# schematic.net
KiCad netlist of a schematic drawn in Altium Designer
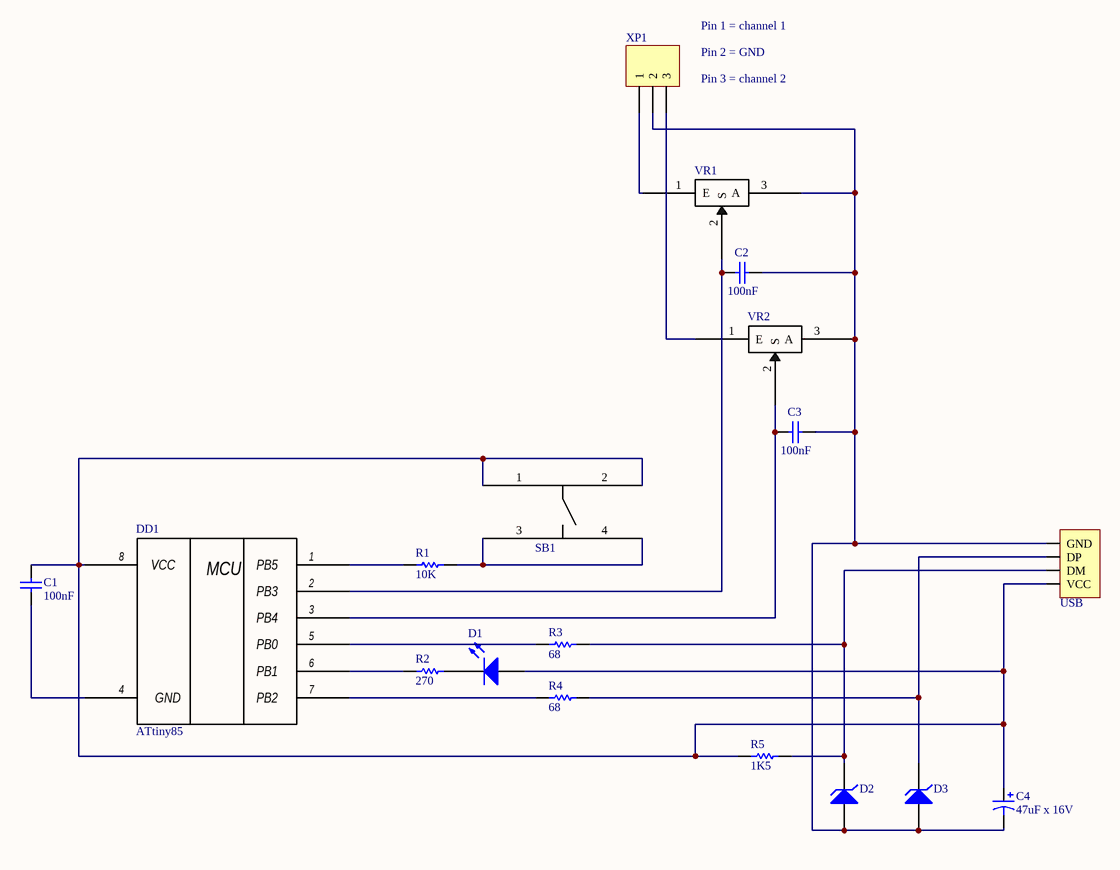
[diagram p0: schematic.SchDoc]

(export (version "E")
  (design (tool "Eeschema 10.0.6"))
  (components
    (comp (ref "C1")
      (value "100nF")
      (footprint "RAD-0.1")
      (description "Capacitor")
      (fields (field (name "PUBLISHER") "Altium Limited"))
      (libsource (lib "Miscellaneous Devices") (part "Cap"))
    )
    (comp (ref "C2")
      (value "100nF")
      (footprint "RAD-0.1")
      (description "Capacitor")
      (fields (field (name "PUBLISHER") "Altium Limited"))
      (libsource (lib "Miscellaneous Devices") (part "Cap"))
    )
    (comp (ref "C3")
      (value "100nF")
      (footprint "RAD-0.1")
      (description "Capacitor")
      (fields (field (name "PUBLISHER") "Altium Limited"))
      (libsource (lib "Miscellaneous Devices") (part "Cap"))
    )
    (comp (ref "C4")
      (value "47uF x 16V")
      (footprint "HDR1X2")
      (description "Polarized Capacitor (Radial)")
      (fields (field (name "PUBLISHER") "Altium Limited"))
      (libsource (lib "Miscellaneous Devices") (part "Cap Pol1"))
    )
    (comp (ref "D1")
      (value "~")
      (footprint "HDR1X2")
      (description "Typical RED GaAs LED")
      (fields (field (name "PUBLISHER") "Altium Limited"))
      (libsource (lib "Miscellaneous Devices") (part "LED1"))
    )
    (comp (ref "D2")
      (value "Zener")
      (footprint "DO-35")
      (description "Zener Diode")
      (fields (field (name "PUBLISHER") "Altium Limited"))
      (libsource (lib "Miscellaneous Devices") (part "D Zener"))
    )
    (comp (ref "D3")
      (value "Zener")
      (footprint "DO-35")
      (description "Zener Diode")
      (fields (field (name "PUBLISHER") "Altium Limited"))
      (libsource (lib "Miscellaneous Devices") (part "D Zener"))
    )
    (comp (ref "DD1")
      (value "ATtiny85")
      (footprint "DIP-8-300")
      (description "8-bit AVR MCU")
      (fields (field (name "PUBLISHER") "Victor Grigoryev"))
      (libsource (lib "Schlib1") (part "ATtiny85"))
    )
    (comp (ref "R1")
      (value "10K")
      (footprint "AXIAL-0.3")
      (description "Resistor")
      (fields (field (name "PUBLISHER") "Altium Limited"))
      (libsource (lib "Miscellaneous Devices") (part "Res1"))
    )
    (comp (ref "R2")
      (value "270")
      (footprint "AXIAL-0.3")
      (description "Resistor")
      (fields (field (name "PUBLISHER") "Altium Limited"))
      (libsource (lib "Miscellaneous Devices") (part "Res1"))
    )
    (comp (ref "R3")
      (value "68")
      (footprint "AXIAL-0.3")
      (description "Resistor")
      (fields (field (name "PUBLISHER") "Altium Limited"))
      (libsource (lib "Miscellaneous Devices") (part "Res1"))
    )
    (comp (ref "R4")
      (value "68")
      (footprint "AXIAL-0.3")
      (description "Resistor")
      (fields (field (name "PUBLISHER") "Altium Limited"))
      (libsource (lib "Miscellaneous Devices") (part "Res1"))
    )
    (comp (ref "R5")
      (value "1K5")
      (footprint "AXIAL-0.3")
      (description "Resistor")
      (fields (field (name "PUBLISHER") "Altium Limited"))
      (libsource (lib "Miscellaneous Devices") (part "Res1"))
    )
    (comp (ref "SB1")
      (value "Button TACT-64K")
      (footprint "Button TACT-64K")
      (description "My standart switch button")
      (fields (field (name "PUBLISHER") "Victor Grigoryev"))
      (libsource (lib "Schlib1") (part "Button TACT-64K"))
    )
    (comp (ref "USB")
      (value "USB_TypeB")
      (footprint "PCB_USB:USB_TypeB")
      (description "USB")
      (libsource (lib "SCH_USB") (part "USB_TypeB"))
    )
    (comp (ref "VR1")
      (value "Potentiometer")
      (footprint "Potentiometer")
      (fields (field (name "PUBLISHER") "Victor Grigoryev"))
      (libsource (lib "Schlib1") (part "Potentiometer"))
    )
    (comp (ref "VR2")
      (value "Potentiometer")
      (footprint "Potentiometer")
      (fields (field (name "PUBLISHER") "Victor Grigoryev"))
      (libsource (lib "Schlib1") (part "Potentiometer"))
    )
    (comp (ref "XP1")
      (value "WF-03R")
      (footprint "HDR1X3")
      (description "Header, 3-Pin")
      (fields (field (name "PUBLISHER") "Altium Limited"))
      (libsource (lib "Miscellaneous Connectors") (part "Header 3"))
    )
  )
  (nets
    (net (code "1") (name "Net-(D1-A)") (class "Default")
      (node (ref "C1") (pin "2") (pinfunction "2_2") (pintype "passive"))
      (node (ref "C4") (pin "1") (pinfunction "1_1") (pintype "passive"))
      (node (ref "D1") (pin "1") (pinfunction "A_1") (pintype "passive"))
      (node (ref "DD1") (pin "8") (pinfunction "VCC_8") (pintype "passive"))
      (node (ref "R5") (pin "2") (pinfunction "2_2") (pintype "passive"))
      (node (ref "SB1") (pin "1") (pinfunction "1_1") (pintype "passive"))
      (node (ref "SB1") (pin "2") (pinfunction "2_2") (pintype "passive"))
      (node (ref "USB") (pin "1") (pinfunction "VCC_1") (pintype "passive"))
    )
    (net (code "2") (name "Net-(D1-K)") (class "Default")
      (node (ref "D1") (pin "2") (pinfunction "K_2") (pintype "passive"))
      (node (ref "R2") (pin "2") (pinfunction "2_2") (pintype "passive"))
    )
    (net (code "3") (name "Net-(D2-A)") (class "Default")
      (node (ref "C2") (pin "1") (pinfunction "1_1") (pintype "passive"))
      (node (ref "C3") (pin "1") (pinfunction "1_1") (pintype "passive"))
      (node (ref "C4") (pin "2") (pinfunction "2_2") (pintype "passive"))
      (node (ref "D2") (pin "1") (pinfunction "A_1") (pintype "passive"))
      (node (ref "D3") (pin "1") (pinfunction "A_1") (pintype "passive"))
      (node (ref "USB") (pin "4") (pinfunction "GND_4") (pintype "passive"))
      (node (ref "VR1") (pin "3") (pinfunction "A_3") (pintype "passive"))
      (node (ref "VR2") (pin "3") (pinfunction "A_3") (pintype "passive"))
      (node (ref "XP1") (pin "2") (pinfunction "2_2") (pintype "passive"))
    )
    (net (code "4") (name "Net-(D2-K)") (class "Default")
      (node (ref "D2") (pin "2") (pinfunction "K_2") (pintype "passive"))
      (node (ref "R3") (pin "2") (pinfunction "2_2") (pintype "passive"))
      (node (ref "R5") (pin "1") (pinfunction "1_1") (pintype "passive"))
      (node (ref "USB") (pin "2") (pinfunction "DM_2") (pintype "passive"))
    )
    (net (code "5") (name "Net-(D3-K)") (class "Default")
      (node (ref "D3") (pin "2") (pinfunction "K_2") (pintype "passive"))
      (node (ref "R4") (pin "2") (pinfunction "2_2") (pintype "passive"))
      (node (ref "USB") (pin "3") (pinfunction "DP_3") (pintype "passive"))
    )
    (net (code "6") (name "Net-(DD1-GND)") (class "Default")
      (node (ref "C1") (pin "1") (pinfunction "1_1") (pintype "passive"))
      (node (ref "DD1") (pin "4") (pinfunction "GND_4") (pintype "passive"))
    )
    (net (code "7") (name "Net-(DD1-PB0)") (class "Default")
      (node (ref "DD1") (pin "5") (pinfunction "PB0_5") (pintype "passive"))
      (node (ref "R3") (pin "1") (pinfunction "1_1") (pintype "passive"))
    )
    (net (code "8") (name "Net-(DD1-PB1)") (class "Default")
      (node (ref "DD1") (pin "6") (pinfunction "PB1_6") (pintype "passive"))
      (node (ref "R2") (pin "1") (pinfunction "1_1") (pintype "passive"))
    )
    (net (code "9") (name "Net-(DD1-PB2)") (class "Default")
      (node (ref "DD1") (pin "7") (pinfunction "PB2_7") (pintype "passive"))
      (node (ref "R4") (pin "1") (pinfunction "1_1") (pintype "passive"))
    )
    (net (code "10") (name "Net-(DD1-PB3)") (class "Default")
      (node (ref "C2") (pin "2") (pinfunction "2_2") (pintype "passive"))
      (node (ref "DD1") (pin "2") (pinfunction "PB3_2") (pintype "passive"))
      (node (ref "VR1") (pin "2") (pinfunction "S_2") (pintype "passive"))
    )
    (net (code "11") (name "Net-(DD1-PB4)") (class "Default")
      (node (ref "C3") (pin "2") (pinfunction "2_2") (pintype "passive"))
      (node (ref "DD1") (pin "3") (pinfunction "PB4_3") (pintype "passive"))
      (node (ref "VR2") (pin "2") (pinfunction "S_2") (pintype "passive"))
    )
    (net (code "12") (name "Net-(DD1-PB5)") (class "Default")
      (node (ref "DD1") (pin "1") (pinfunction "PB5_1") (pintype "passive"))
      (node (ref "R1") (pin "1") (pinfunction "1_1") (pintype "passive"))
    )
    (net (code "13") (name "Net-(R1-Pad2)") (class "Default")
      (node (ref "R1") (pin "2") (pinfunction "2_2") (pintype "passive"))
      (node (ref "SB1") (pin "3") (pinfunction "3_3") (pintype "passive"))
      (node (ref "SB1") (pin "4") (pinfunction "4_4") (pintype "passive"))
    )
    (net (code "14") (name "Net-(VR1-E)") (class "Default")
      (node (ref "VR1") (pin "1") (pinfunction "E_1") (pintype "passive"))
      (node (ref "XP1") (pin "1") (pinfunction "1_1") (pintype "passive"))
    )
    (net (code "15") (name "Net-(VR2-E)") (class "Default")
      (node (ref "VR2") (pin "1") (pinfunction "E_1") (pintype "passive"))
      (node (ref "XP1") (pin "3") (pinfunction "3_3") (pintype "passive"))
    )
  )
)
